# RTL8201CP.net
KiCad netlist of a schematic drawn in Altium Designer
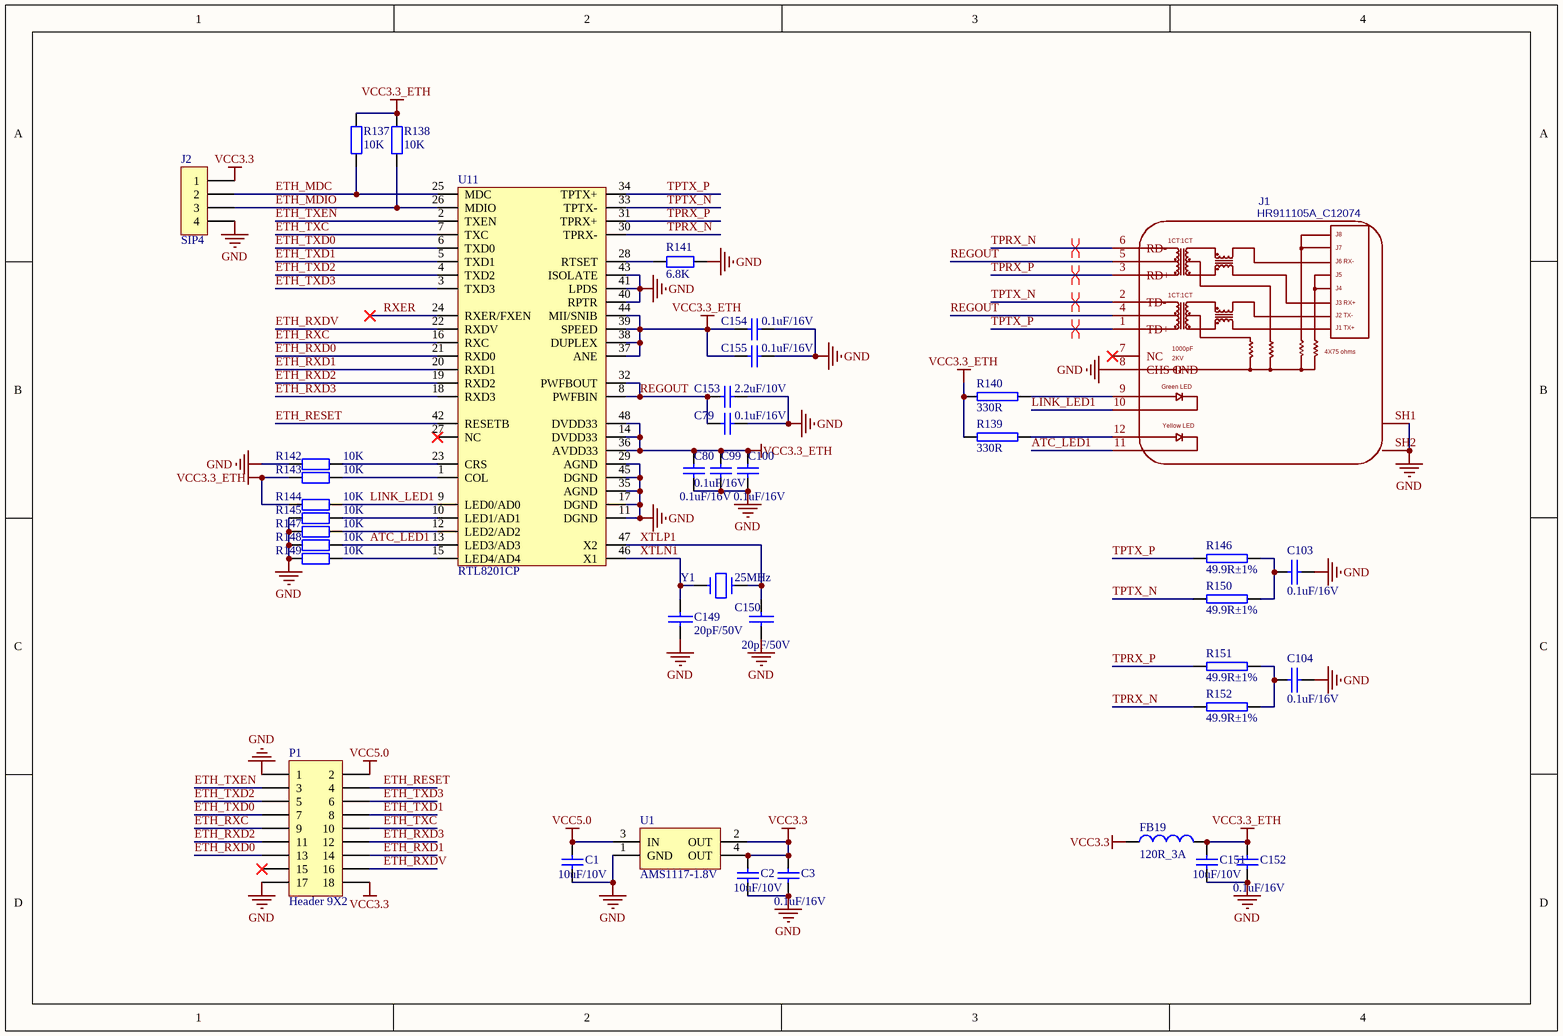
[diagram p0: RTL8201CP.SchDoc]

(export (version "E")
  (design (tool "Eeschema 10.0.6"))
  (components
    (comp (ref "C1")
      (value "10uF/10V")
      (footprint "0402C")
      (description "10uF_10%_X5R_25V")
      (libsource (lib "MySchlibraries") (part "CT41-25V-0805-106"))
    )
    (comp (ref "C2")
      (value "10uF/10V")
      (footprint "0402C")
      (description "10uF_10%_X5R_25V")
      (libsource (lib "MySchlibraries") (part "CT41-25V-0805-106"))
    )
    (comp (ref "C3")
      (value "0.1uF/16V")
      (footprint "0402C")
      (description "0.1uF_10%_X5R_50V")
      (libsource (lib "MySchlibraries") (part "CT41-50V-0805-104"))
    )
    (comp (ref "C79")
      (value "0.1uF/16V")
      (footprint "0402C")
      (description "0.1uF_10%_X5R_50V")
      (libsource (lib "MySchlibraries") (part "CT41-50V-0805-104"))
    )
    (comp (ref "C80")
      (value "0.1uF/16V")
      (footprint "0402C")
      (description "0.1uF_10%_X5R_50V")
      (libsource (lib "MySchlibraries") (part "CT41-50V-0805-104"))
    )
    (comp (ref "C99")
      (value "0.1uF/16V")
      (footprint "0402C")
      (description "0.1uF_10%_X5R_50V")
      (libsource (lib "MySchlibraries") (part "CT41-50V-0805-104"))
    )
    (comp (ref "C100")
      (value "0.1uF/16V")
      (footprint "0402C")
      (description "0.1uF_10%_X5R_50V")
      (libsource (lib "MySchlibraries") (part "CT41-50V-0805-104"))
    )
    (comp (ref "C103")
      (value "0.1uF/16V")
      (footprint "0402C")
      (description "Capacitor")
      (libsource (lib "我的元件库") (part "CAP"))
    )
    (comp (ref "C104")
      (value "0.1uF/16V")
      (footprint "0402C")
      (description "Capacitor")
      (libsource (lib "我的元件库") (part "CAP"))
    )
    (comp (ref "C149")
      (value "20pF/50V")
      (footprint "0402C")
      (description "Capacitor")
      (libsource (lib "我的元件库") (part "CAP"))
    )
    (comp (ref "C150")
      (value "20pF/50V")
      (footprint "0402C")
      (description "Capacitor")
      (libsource (lib "我的元件库") (part "CAP"))
    )
    (comp (ref "C151")
      (value "10uF/10V")
      (footprint "0402C")
      (description "10uF_10%_X5R_25V")
      (libsource (lib "MySchlibraries") (part "CT41-25V-0805-106"))
    )
    (comp (ref "C152")
      (value "0.1uF/16V")
      (footprint "0402C")
      (description "0.1uF_10%_X5R_50V")
      (libsource (lib "MySchlibraries") (part "CT41-50V-0805-104"))
    )
    (comp (ref "C153")
      (value "2.2uF/10V")
      (footprint "0402C")
      (description "0.1uF_10%_X5R_50V")
      (libsource (lib "MySchlibraries") (part "CT41-50V-0805-104"))
    )
    (comp (ref "C154")
      (value "0.1uF/16V")
      (footprint "0402C")
      (description "0.1uF_10%_X5R_50V")
      (libsource (lib "MySchlibraries") (part "CT41-50V-0805-104"))
    )
    (comp (ref "C155")
      (value "0.1uF/16V")
      (footprint "0402C")
      (description "0.1uF_10%_X5R_50V")
      (libsource (lib "MySchlibraries") (part "CT41-50V-0805-104"))
    )
    (comp (ref "FB19") (value "120R_3A") (footprint "0603") (libsource (lib "我的元件库") (part "FB-90R-100Mhz")))
    (comp (ref "J1")
      (value "HR911105A_C12074")
      (footprint "RJ45-TH_HR911105A")
      (fields (field (name "BOM_MANUFACTURER PART") "HR911105A") (field (name "BOM_SUPPLIER PART") "C12074"))
      (libsource (lib "altium-import") (part "root_0_HR911105A_C12074_"))
    )
    (comp (ref "J2") (value "SIP4") (footprint "SIP4") (libsource (lib "我的元件库") (part "CON4")))
    (comp (ref "P1")
      (value "Header 9X2")
      (footprint "HDR2X9")
      (description "Header, 9-Pin, Dual row")
      (fields (field (name "PUBLISHER") "Altium Limited"))
      (libsource (lib "Miscellaneous Connectors") (part "Header 9X2"))
    )
    (comp (ref "R137")
      (value "10K")
      (footprint "0402R")
      (description "0R_5%_1/16W")
      (libsource (lib "MySchlibraries") (part "RC-0805-0R"))
    )
    (comp (ref "R138")
      (value "10K")
      (footprint "0402R")
      (description "0R_5%_1/16W")
      (libsource (lib "MySchlibraries") (part "RC-0805-0R"))
    )
    (comp (ref "R139") (value "330R") (footprint "0402R") (libsource (lib "我的元件库") (part "RES")))
    (comp (ref "R140") (value "330R") (footprint "0402R") (libsource (lib "我的元件库") (part "RES")))
    (comp (ref "R141")
      (value "6.8K")
      (footprint "0402R")
      (description "0R_5%_1/16W")
      (libsource (lib "MySchlibraries") (part "RC-0805-0R"))
    )
    (comp (ref "R142")
      (value "10K")
      (footprint "0402R")
      (description "0R_5%_1/16W")
      (libsource (lib "MySchlibraries") (part "RC-0805-0R"))
    )
    (comp (ref "R143")
      (value "10K")
      (footprint "0402R")
      (description "0R_5%_1/16W")
      (libsource (lib "MySchlibraries") (part "RC-0805-0R"))
    )
    (comp (ref "R144")
      (value "10K")
      (footprint "0402R")
      (description "0R_5%_1/16W")
      (libsource (lib "MySchlibraries") (part "RC-0805-0R"))
    )
    (comp (ref "R145")
      (value "10K")
      (footprint "0402R")
      (description "0R_5%_1/16W")
      (libsource (lib "MySchlibraries") (part "RC-0805-0R"))
    )
    (comp (ref "R146") (value "49.9R±1%") (footprint "0402R") (libsource (lib "我的元件库") (part "RES")))
    (comp (ref "R147")
      (value "10K")
      (footprint "0402R")
      (description "0R_5%_1/16W")
      (libsource (lib "MySchlibraries") (part "RC-0805-0R"))
    )
    (comp (ref "R148")
      (value "10K")
      (footprint "0402R")
      (description "0R_5%_1/16W")
      (libsource (lib "MySchlibraries") (part "RC-0805-0R"))
    )
    (comp (ref "R149")
      (value "10K")
      (footprint "0402R")
      (description "0R_5%_1/16W")
      (libsource (lib "MySchlibraries") (part "RC-0805-0R"))
    )
    (comp (ref "R150") (value "49.9R±1%") (footprint "0402R") (libsource (lib "我的元件库") (part "RES")))
    (comp (ref "R151") (value "49.9R±1%") (footprint "0402R") (libsource (lib "我的元件库") (part "RES")))
    (comp (ref "R152") (value "49.9R±1%") (footprint "0402R") (libsource (lib "我的元件库") (part "RES")))
    (comp (ref "U1")
      (value "AMS1117-1.8V")
      (footprint "SOT-223")
      (description "稳压器1.8V")
      (fields (field (name "ALTIUM_UNNAMED_1") "AMS1117-1.8V"))
      (libsource (lib "我的元件库") (part "AMS1117-1.8V"))
    )
    (comp (ref "U11")
      (value "RTL8201CP")
      (footprint "LQFP48S")
      (description "ETH PHY")
      (libsource (lib "PIONEER") (part "RTL8201CP"))
    )
    (comp (ref "Y1") (value "25MHz") (footprint "HC-49S") (libsource (lib "我的元件库") (part "CRYES")))
  )
  (nets
    (net (code "1") (name "/ATC_LED1") (class "Default")
      (node (ref "J1") (pin "11") (pinfunction "11_11") (pintype "passive"))
      (node (ref "R148") (pin "1") (pinfunction "1_1") (pintype "passive"))
      (node (ref "U11") (pin "13") (pinfunction "LED3/AD3_13") (pintype "passive"))
    )
    (net (code "2") (name "/ETH_MDC") (class "Default")
      (node (ref "J2") (pin "2") (pinfunction "2_2") (pintype "passive"))
      (node (ref "R137") (pin "1") (pinfunction "1_1") (pintype "passive"))
      (node (ref "U11") (pin "25") (pinfunction "MDC_25") (pintype "passive"))
    )
    (net (code "3") (name "/ETH_MDIO") (class "Default")
      (node (ref "J2") (pin "3") (pinfunction "3_3") (pintype "passive"))
      (node (ref "R138") (pin "1") (pinfunction "1_1") (pintype "passive"))
      (node (ref "U11") (pin "26") (pinfunction "MDIO_26") (pintype "passive"))
    )
    (net (code "4") (name "/ETH_RESET") (class "Default")
      (node (ref "P1") (pin "4") (pinfunction "4_4") (pintype "passive"))
      (node (ref "U11") (pin "42") (pinfunction "RESETB_42") (pintype "passive"))
    )
    (net (code "5") (name "/ETH_RXC") (class "Default")
      (node (ref "P1") (pin "9") (pinfunction "9_9") (pintype "passive"))
      (node (ref "U11") (pin "16") (pinfunction "RXC_16") (pintype "passive"))
    )
    (net (code "6") (name "/ETH_RXD0") (class "Default")
      (node (ref "P1") (pin "13") (pinfunction "13_13") (pintype "passive"))
      (node (ref "U11") (pin "21") (pinfunction "RXD0_21") (pintype "passive"))
    )
    (net (code "7") (name "/ETH_RXD1") (class "Default")
      (node (ref "P1") (pin "14") (pinfunction "14_14") (pintype "passive"))
      (node (ref "U11") (pin "20") (pinfunction "RXD1_20") (pintype "passive"))
    )
    (net (code "8") (name "/ETH_RXD2") (class "Default")
      (node (ref "P1") (pin "11") (pinfunction "11_11") (pintype "passive"))
      (node (ref "U11") (pin "19") (pinfunction "RXD2_19") (pintype "passive"))
    )
    (net (code "9") (name "/ETH_RXD3") (class "Default")
      (node (ref "P1") (pin "12") (pinfunction "12_12") (pintype "passive"))
      (node (ref "U11") (pin "18") (pinfunction "RXD3_18") (pintype "passive"))
    )
    (net (code "10") (name "/ETH_RXDV") (class "Default")
      (node (ref "P1") (pin "16") (pinfunction "16_16") (pintype "passive"))
      (node (ref "U11") (pin "22") (pinfunction "RXDV_22") (pintype "passive"))
    )
    (net (code "11") (name "/ETH_TXC") (class "Default")
      (node (ref "P1") (pin "10") (pinfunction "10_10") (pintype "passive"))
      (node (ref "U11") (pin "7") (pinfunction "TXC_7") (pintype "passive"))
    )
    (net (code "12") (name "/ETH_TXD0") (class "Default")
      (node (ref "P1") (pin "7") (pinfunction "7_7") (pintype "passive"))
      (node (ref "U11") (pin "6") (pinfunction "TXD0_6") (pintype "passive"))
    )
    (net (code "13") (name "/ETH_TXD1") (class "Default")
      (node (ref "P1") (pin "8") (pinfunction "8_8") (pintype "passive"))
      (node (ref "U11") (pin "5") (pinfunction "TXD1_5") (pintype "passive"))
    )
    (net (code "14") (name "/ETH_TXD2") (class "Default")
      (node (ref "P1") (pin "5") (pinfunction "5_5") (pintype "passive"))
      (node (ref "U11") (pin "4") (pinfunction "TXD2_4") (pintype "passive"))
    )
    (net (code "15") (name "/ETH_TXD3") (class "Default")
      (node (ref "P1") (pin "6") (pinfunction "6_6") (pintype "passive"))
      (node (ref "U11") (pin "3") (pinfunction "TXD3_3") (pintype "passive"))
    )
    (net (code "16") (name "/ETH_TXEN") (class "Default")
      (node (ref "P1") (pin "3") (pinfunction "3_3") (pintype "passive"))
      (node (ref "U11") (pin "2") (pinfunction "TXEN_2") (pintype "passive"))
    )
    (net (code "17") (name "/LINK_LED1") (class "Default")
      (node (ref "J1") (pin "10") (pinfunction "10_10") (pintype "passive"))
      (node (ref "R144") (pin "1") (pinfunction "1_1") (pintype "passive"))
      (node (ref "U11") (pin "9") (pinfunction "LED0/AD0_9") (pintype "passive"))
    )
    (net (code "18") (name "/REGOUT") (class "Default")
      (node (ref "C153") (pin "2") (pinfunction "2_2") (pintype "passive"))
      (node (ref "C79") (pin "2") (pinfunction "2_2") (pintype "passive"))
      (node (ref "J1") (pin "4") (pinfunction "4_4") (pintype "passive"))
      (node (ref "J1") (pin "5") (pinfunction "5_5") (pintype "passive"))
      (node (ref "U11") (pin "32") (pinfunction "PWFBOUT_32") (pintype "passive"))
      (node (ref "U11") (pin "8") (pinfunction "PWFBIN_8") (pintype "passive"))
    )
    (net (code "19") (name "/RXER") (class "Default")
      (node (ref "U11") (pin "24") (pinfunction "RXER/FXEN_24") (pintype "passive+no_connect"))
    )
    (net (code "20") (name "/TPRX_N") (class "Default")
      (node (ref "J1") (pin "6") (pinfunction "RD-_6") (pintype "passive"))
      (node (ref "R152") (pin "2") (pinfunction "2_2") (pintype "passive"))
      (node (ref "U11") (pin "30") (pinfunction "TPRX-_30") (pintype "passive"))
    )
    (net (code "21") (name "/TPRX_P") (class "Default")
      (node (ref "J1") (pin "3") (pinfunction "RD+_3") (pintype "passive"))
      (node (ref "R151") (pin "2") (pinfunction "2_2") (pintype "passive"))
      (node (ref "U11") (pin "31") (pinfunction "TPRX+_31") (pintype "passive"))
    )
    (net (code "22") (name "/TPTX_N") (class "Default")
      (node (ref "J1") (pin "2") (pinfunction "TD-_2") (pintype "passive"))
      (node (ref "R150") (pin "2") (pinfunction "2_2") (pintype "passive"))
      (node (ref "U11") (pin "33") (pinfunction "TPTX-_33") (pintype "passive"))
    )
    (net (code "23") (name "/TPTX_P") (class "Default")
      (node (ref "J1") (pin "1") (pinfunction "TD+_1") (pintype "passive"))
      (node (ref "R146") (pin "2") (pinfunction "2_2") (pintype "passive"))
      (node (ref "U11") (pin "34") (pinfunction "TPTX+_34") (pintype "passive"))
    )
    (net (code "24") (name "/XTLN1") (class "Default")
      (node (ref "C149") (pin "1") (pinfunction "1_1") (pintype "passive"))
      (node (ref "U11") (pin "46") (pinfunction "X1_46") (pintype "passive"))
      (node (ref "Y1") (pin "1") (pinfunction "1_1") (pintype "passive"))
    )
    (net (code "25") (name "/XTLP1") (class "Default")
      (node (ref "C150") (pin "2") (pinfunction "2_2") (pintype "passive"))
      (node (ref "U11") (pin "47") (pinfunction "X2_47") (pintype "passive"))
      (node (ref "Y1") (pin "2") (pinfunction "2_2") (pintype "passive"))
    )
    (net (code "26") (name "GND") (class "Default")
      (node (ref "C1") (pin "1") (pinfunction "1_1") (pintype "passive"))
      (node (ref "C100") (pin "1") (pinfunction "1_1") (pintype "passive"))
      (node (ref "C103") (pin "1") (pinfunction "1_1") (pintype "passive"))
      (node (ref "C104") (pin "1") (pinfunction "1_1") (pintype "passive"))
      (node (ref "C149") (pin "2") (pinfunction "2_2") (pintype "passive"))
      (node (ref "C150") (pin "1") (pinfunction "1_1") (pintype "passive"))
      (node (ref "C151") (pin "1") (pinfunction "1_1") (pintype "passive"))
      (node (ref "C152") (pin "1") (pinfunction "1_1") (pintype "passive"))
      (node (ref "C153") (pin "1") (pinfunction "1_1") (pintype "passive"))
      (node (ref "C154") (pin "1") (pinfunction "1_1") (pintype "passive"))
      (node (ref "C155") (pin "1") (pinfunction "1_1") (pintype "passive"))
      (node (ref "C2") (pin "1") (pinfunction "1_1") (pintype "passive"))
      (node (ref "C3") (pin "1") (pinfunction "1_1") (pintype "passive"))
      (node (ref "C79") (pin "1") (pinfunction "1_1") (pintype "passive"))
      (node (ref "C80") (pin "1") (pinfunction "1_1") (pintype "passive"))
      (node (ref "C99") (pin "1") (pinfunction "1_1") (pintype "passive"))
      (node (ref "J1") (pin "8") (pinfunction "CHS_GND_8") (pintype "passive"))
      (node (ref "J1") (pin "SH1") (pinfunction "SH1_SH1") (pintype "passive"))
      (node (ref "J1") (pin "SH2") (pinfunction "SH2_SH2") (pintype "passive"))
      (node (ref "J2") (pin "4") (pinfunction "4_4") (pintype "passive"))
      (node (ref "P1") (pin "1") (pinfunction "1_1") (pintype "passive"))
      (node (ref "P1") (pin "17") (pinfunction "17_17") (pintype "passive"))
      (node (ref "R141") (pin "1") (pinfunction "1_1") (pintype "passive"))
      (node (ref "R142") (pin "2") (pinfunction "2_2") (pintype "passive"))
      (node (ref "R145") (pin "2") (pinfunction "2_2") (pintype "passive"))
      (node (ref "R147") (pin "2") (pinfunction "2_2") (pintype "passive"))
      (node (ref "R148") (pin "2") (pinfunction "2_2") (pintype "passive"))
      (node (ref "R149") (pin "2") (pinfunction "2_2") (pintype "passive"))
      (node (ref "U1") (pin "1") (pinfunction "GND_1") (pintype "power_in"))
      (node (ref "U11") (pin "11") (pinfunction "DGND_11") (pintype "passive"))
      (node (ref "U11") (pin "17") (pinfunction "DGND_17") (pintype "passive"))
      (node (ref "U11") (pin "29") (pinfunction "AGND_29") (pintype "passive"))
      (node (ref "U11") (pin "35") (pinfunction "AGND_35") (pintype "passive"))
      (node (ref "U11") (pin "40") (pinfunction "RPTR_40") (pintype "passive"))
      (node (ref "U11") (pin "41") (pinfunction "LPDS_41") (pintype "passive"))
      (node (ref "U11") (pin "43") (pinfunction "ISOLATE_43") (pintype "passive"))
      (node (ref "U11") (pin "45") (pinfunction "DGND_45") (pintype "passive"))
    )
    (net (code "27") (name "Net-(C103-Pad2)") (class "Default")
      (node (ref "C103") (pin "2") (pinfunction "2_2") (pintype "passive"))
      (node (ref "R146") (pin "1") (pinfunction "1_1") (pintype "passive"))
      (node (ref "R150") (pin "1") (pinfunction "1_1") (pintype "passive"))
    )
    (net (code "28") (name "Net-(C104-Pad2)") (class "Default")
      (node (ref "C104") (pin "2") (pinfunction "2_2") (pintype "passive"))
      (node (ref "R151") (pin "1") (pinfunction "1_1") (pintype "passive"))
      (node (ref "R152") (pin "1") (pinfunction "1_1") (pintype "passive"))
    )
    (net (code "29") (name "Net-(J1-Pad9)") (class "Default")
      (node (ref "J1") (pin "9") (pinfunction "9_9") (pintype "passive"))
      (node (ref "R140") (pin "1") (pinfunction "1_1") (pintype "passive"))
    )
    (net (code "30") (name "Net-(J1-Pad12)") (class "Default")
      (node (ref "J1") (pin "12") (pinfunction "12_12") (pintype "passive"))
      (node (ref "R139") (pin "1") (pinfunction "1_1") (pintype "passive"))
    )
    (net (code "31") (name "Net-(U11-COL)") (class "Default")
      (node (ref "R143") (pin "1") (pinfunction "1_1") (pintype "passive"))
      (node (ref "U11") (pin "1") (pinfunction "COL_1") (pintype "passive"))
    )
    (net (code "32") (name "Net-(U11-CRS)") (class "Default")
      (node (ref "R142") (pin "1") (pinfunction "1_1") (pintype "passive"))
      (node (ref "U11") (pin "23") (pinfunction "CRS_23") (pintype "passive"))
    )
    (net (code "33") (name "Net-(U11-LED1{slash}AD1)") (class "Default")
      (node (ref "R145") (pin "1") (pinfunction "1_1") (pintype "passive"))
      (node (ref "U11") (pin "10") (pinfunction "LED1/AD1_10") (pintype "passive"))
    )
    (net (code "34") (name "Net-(U11-LED2{slash}AD2)") (class "Default")
      (node (ref "R147") (pin "1") (pinfunction "1_1") (pintype "passive"))
      (node (ref "U11") (pin "12") (pinfunction "LED2/AD2_12") (pintype "passive"))
    )
    (net (code "35") (name "Net-(U11-LED4{slash}AD4)") (class "Default")
      (node (ref "R149") (pin "1") (pinfunction "1_1") (pintype "passive"))
      (node (ref "U11") (pin "15") (pinfunction "LED4/AD4_15") (pintype "passive"))
    )
    (net (code "36") (name "Net-(U11-RTSET)") (class "Default")
      (node (ref "R141") (pin "2") (pinfunction "2_2") (pintype "passive"))
      (node (ref "U11") (pin "28") (pinfunction "RTSET_28") (pintype "passive"))
    )
    (net (code "37") (name "VCC3.3") (class "Default")
      (node (ref "C2") (pin "2") (pinfunction "2_2") (pintype "passive"))
      (node (ref "C3") (pin "2") (pinfunction "2_2") (pintype "passive"))
      (node (ref "FB19") (pin "1") (pinfunction "1_1") (pintype "passive"))
      (node (ref "J2") (pin "1") (pinfunction "1_1") (pintype "passive"))
      (node (ref "P1") (pin "18") (pinfunction "18_18") (pintype "passive"))
      (node (ref "U1") (pin "2") (pinfunction "OUT_2") (pintype "power_in"))
      (node (ref "U1") (pin "4") (pinfunction "OUT_4") (pintype "power_in"))
    )
    (net (code "38") (name "VCC3.3_ETH") (class "Default")
      (node (ref "C100") (pin "2") (pinfunction "2_2") (pintype "passive"))
      (node (ref "C151") (pin "2") (pinfunction "2_2") (pintype "passive"))
      (node (ref "C152") (pin "2") (pinfunction "2_2") (pintype "passive"))
      (node (ref "C154") (pin "2") (pinfunction "2_2") (pintype "passive"))
      (node (ref "C155") (pin "2") (pinfunction "2_2") (pintype "passive"))
      (node (ref "C80") (pin "2") (pinfunction "2_2") (pintype "passive"))
      (node (ref "C99") (pin "2") (pinfunction "2_2") (pintype "passive"))
      (node (ref "FB19") (pin "2") (pinfunction "2_2") (pintype "passive"))
      (node (ref "R137") (pin "2") (pinfunction "2_2") (pintype "passive"))
      (node (ref "R138") (pin "2") (pinfunction "2_2") (pintype "passive"))
      (node (ref "R139") (pin "2") (pinfunction "2_2") (pintype "passive"))
      (node (ref "R140") (pin "2") (pinfunction "2_2") (pintype "passive"))
      (node (ref "R143") (pin "2") (pinfunction "2_2") (pintype "passive"))
      (node (ref "R144") (pin "2") (pinfunction "2_2") (pintype "passive"))
      (node (ref "U11") (pin "14") (pinfunction "DVDD33_14") (pintype "passive"))
      (node (ref "U11") (pin "36") (pinfunction "AVDD33_36") (pintype "passive"))
      (node (ref "U11") (pin "37") (pinfunction "ANE_37") (pintype "passive"))
      (node (ref "U11") (pin "38") (pinfunction "DUPLEX_38") (pintype "passive"))
      (node (ref "U11") (pin "39") (pinfunction "SPEED_39") (pintype "passive"))
      (node (ref "U11") (pin "44") (pinfunction "MII/SNIB_44") (pintype "passive"))
      (node (ref "U11") (pin "48") (pinfunction "DVDD33_48") (pintype "passive"))
    )
    (net (code "39") (name "VCC5.0") (class "Default")
      (node (ref "C1") (pin "2") (pinfunction "2_2") (pintype "passive"))
      (node (ref "P1") (pin "2") (pinfunction "2_2") (pintype "passive"))
      (node (ref "U1") (pin "3") (pinfunction "IN_3") (pintype "power_in"))
    )
    (net (code "40") (name "unconnected-(J1-NC-Pad7)") (class "Default")
      (node (ref "J1") (pin "7") (pinfunction "NC_7") (pintype "passive+no_connect"))
    )
    (net (code "41") (name "unconnected-(P1-Pad15)") (class "Default")
      (node (ref "P1") (pin "15") (pinfunction "15_15") (pintype "passive+no_connect"))
    )
    (net (code "42") (name "unconnected-(U11-NC-Pad27)") (class "Default")
      (node (ref "U11") (pin "27") (pinfunction "NC_27") (pintype "passive+no_connect"))
    )
  )
)
